# Power_Regulation.net
KiCad netlist of a schematic drawn in Altium Designer
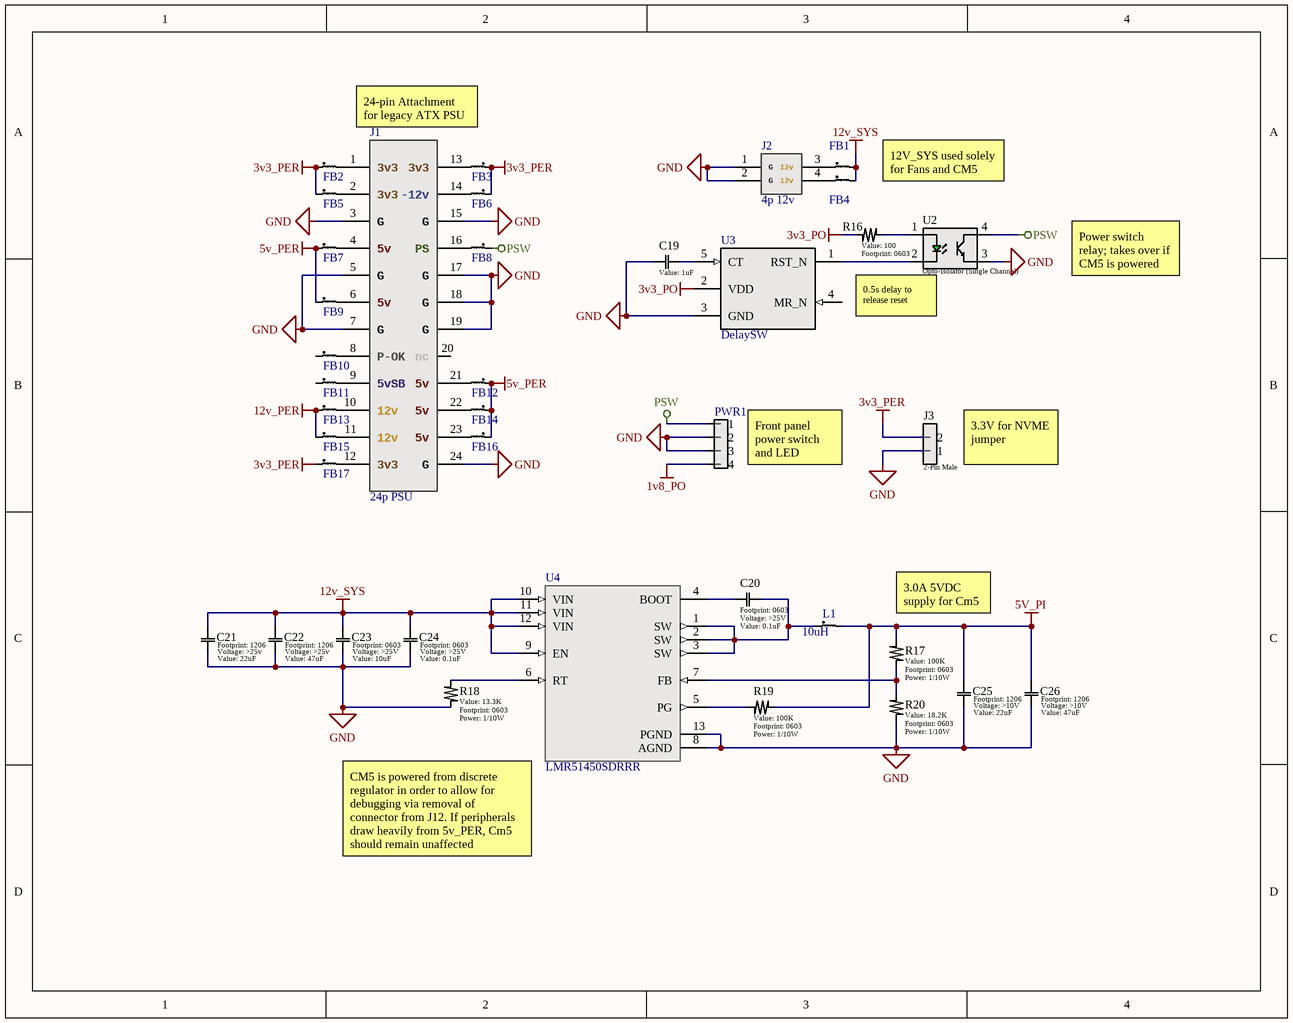
[diagram p0: Power_Regulation.SchDoc]

(export (version "E")
  (design (tool "Eeschema 10.0.6"))
  (components
    (comp (ref "C19")
      (value "1uF")
      (footprint "0603")
      (fields
        (field (name "VOLTAGE") "10V")
        (field (name "TOLERANCE") "10%")
        (field (name "Comment") "Generic Capacitor")
      )
      (libsource (lib "Capacitors") (part "Generic Capacitor"))
    )
    (comp (ref "C20")
      (value "0.1uF")
      (footprint "0603")
      (fields
        (field (name "VOLTAGE") ">25V")
        (field (name "TOLERANCE") "10%")
        (field (name "Comment") "Generic Capacitor")
      )
      (libsource (lib "Capacitors") (part "Generic Capacitor"))
    )
    (comp (ref "C21")
      (value "22uF")
      (footprint "1206")
      (fields
        (field (name "VOLTAGE") ">25v")
        (field (name "TOLERANCE") "20%")
        (field (name "Comment") "Generic Capacitor")
      )
      (libsource (lib "Capacitors") (part "Generic Capacitor"))
    )
    (comp (ref "C22")
      (value "47uF")
      (footprint "1206")
      (fields
        (field (name "VOLTAGE") ">25v")
        (field (name "TOLERANCE") "20%")
        (field (name "Comment") "Generic Capacitor")
      )
      (libsource (lib "Capacitors") (part "Generic Capacitor"))
    )
    (comp (ref "C23")
      (value "10uF")
      (footprint "0603")
      (fields
        (field (name "VOLTAGE") ">25V")
        (field (name "TOLERANCE") "10%")
        (field (name "Comment") "Generic Capacitor")
      )
      (libsource (lib "Capacitors") (part "Generic Capacitor"))
    )
    (comp (ref "C24")
      (value "0.1uF")
      (footprint "0603")
      (fields
        (field (name "VOLTAGE") ">25V")
        (field (name "TOLERANCE") "10%")
        (field (name "Comment") "Generic Capacitor")
      )
      (libsource (lib "Capacitors") (part "Generic Capacitor"))
    )
    (comp (ref "C25")
      (value "22uF")
      (footprint "1206")
      (fields
        (field (name "VOLTAGE") ">10V")
        (field (name "TOLERANCE") "20%")
        (field (name "Comment") "Generic Capacitor")
      )
      (libsource (lib "Capacitors") (part "Generic Capacitor"))
    )
    (comp (ref "C26")
      (value "47uF")
      (footprint "1206")
      (fields
        (field (name "VOLTAGE") ">10V")
        (field (name "TOLERANCE") "10%")
        (field (name "Comment") "Generic Capacitor")
      )
      (libsource (lib "Capacitors") (part "Generic Capacitor"))
    )
    (comp (ref "FB1")
      (value "1206 Ferrite")
      (footprint "1206")
      (description "160 Ohms @ 100MHz 1 Power, Signal Line Ferrite Bead 1206 (3216 Metric) 6A 18mOhm")
      (libsource (lib "Inductors") (part "HI1206T161R-10"))
    )
    (comp (ref "FB2")
      (value "1206 Ferrite")
      (footprint "1206")
      (description "160 Ohms @ 100MHz 1 Power, Signal Line Ferrite Bead 1206 (3216 Metric) 6A 18mOhm")
      (libsource (lib "Inductors") (part "HI1206T161R-10"))
    )
    (comp (ref "FB3")
      (value "1206 Ferrite")
      (footprint "1206")
      (description "160 Ohms @ 100MHz 1 Power, Signal Line Ferrite Bead 1206 (3216 Metric) 6A 18mOhm")
      (libsource (lib "") (part "HI1206T161R-10_1"))
    )
    (comp (ref "FB4")
      (value "1206 Ferrite")
      (footprint "1206")
      (description "160 Ohms @ 100MHz 1 Power, Signal Line Ferrite Bead 1206 (3216 Metric) 6A 18mOhm")
      (libsource (lib "Inductors") (part "HI1206T161R-10"))
    )
    (comp (ref "FB5")
      (value "1206 Ferrite")
      (footprint "1206")
      (description "160 Ohms @ 100MHz 1 Power, Signal Line Ferrite Bead 1206 (3216 Metric) 6A 18mOhm")
      (libsource (lib "Inductors") (part "HI1206T161R-10"))
    )
    (comp (ref "FB6")
      (value "1206 Ferrite")
      (footprint "1206")
      (description "160 Ohms @ 100MHz 1 Power, Signal Line Ferrite Bead 1206 (3216 Metric) 6A 18mOhm")
      (libsource (lib "") (part "HI1206T161R-10_1"))
    )
    (comp (ref "FB7")
      (value "1206 Ferrite")
      (footprint "1206")
      (description "160 Ohms @ 100MHz 1 Power, Signal Line Ferrite Bead 1206 (3216 Metric) 6A 18mOhm")
      (libsource (lib "Inductors") (part "HI1206T161R-10"))
    )
    (comp (ref "FB8")
      (value "1206 Ferrite")
      (footprint "1206")
      (description "160 Ohms @ 100MHz 1 Power, Signal Line Ferrite Bead 1206 (3216 Metric) 6A 18mOhm")
      (libsource (lib "") (part "HI1206T161R-10_1"))
    )
    (comp (ref "FB9")
      (value "1206 Ferrite")
      (footprint "1206")
      (description "160 Ohms @ 100MHz 1 Power, Signal Line Ferrite Bead 1206 (3216 Metric) 6A 18mOhm")
      (libsource (lib "Inductors") (part "HI1206T161R-10"))
    )
    (comp (ref "FB10")
      (value "1206 Ferrite")
      (footprint "1206")
      (description "160 Ohms @ 100MHz 1 Power, Signal Line Ferrite Bead 1206 (3216 Metric) 6A 18mOhm")
      (libsource (lib "Inductors") (part "HI1206T161R-10"))
    )
    (comp (ref "FB11")
      (value "1206 Ferrite")
      (footprint "1206")
      (description "160 Ohms @ 100MHz 1 Power, Signal Line Ferrite Bead 1206 (3216 Metric) 6A 18mOhm")
      (libsource (lib "Inductors") (part "HI1206T161R-10"))
    )
    (comp (ref "FB12")
      (value "1206 Ferrite")
      (footprint "1206")
      (description "160 Ohms @ 100MHz 1 Power, Signal Line Ferrite Bead 1206 (3216 Metric) 6A 18mOhm")
      (libsource (lib "") (part "HI1206T161R-10_1"))
    )
    (comp (ref "FB13")
      (value "1206 Ferrite")
      (footprint "1206")
      (description "160 Ohms @ 100MHz 1 Power, Signal Line Ferrite Bead 1206 (3216 Metric) 6A 18mOhm")
      (libsource (lib "Inductors") (part "HI1206T161R-10"))
    )
    (comp (ref "FB14")
      (value "1206 Ferrite")
      (footprint "1206")
      (description "160 Ohms @ 100MHz 1 Power, Signal Line Ferrite Bead 1206 (3216 Metric) 6A 18mOhm")
      (libsource (lib "") (part "HI1206T161R-10_1"))
    )
    (comp (ref "FB15")
      (value "1206 Ferrite")
      (footprint "1206")
      (description "160 Ohms @ 100MHz 1 Power, Signal Line Ferrite Bead 1206 (3216 Metric) 6A 18mOhm")
      (libsource (lib "Inductors") (part "HI1206T161R-10"))
    )
    (comp (ref "FB16")
      (value "1206 Ferrite")
      (footprint "1206")
      (description "160 Ohms @ 100MHz 1 Power, Signal Line Ferrite Bead 1206 (3216 Metric) 6A 18mOhm")
      (libsource (lib "") (part "HI1206T161R-10_1"))
    )
    (comp (ref "FB17")
      (value "1206 Ferrite")
      (footprint "1206")
      (description "160 Ohms @ 100MHz 1 Power, Signal Line Ferrite Bead 1206 (3216 Metric) 6A 18mOhm")
      (libsource (lib "Inductors") (part "HI1206T161R-10"))
    )
    (comp (ref "J1")
      (value "24p PSU")
      (footprint "CONN_442060007_MOL")
      (description "Connector Header Through Hole 24 position 0.165\" (4.20mm)")
      (libsource (lib "Connectors") (part "442060007"))
    )
    (comp (ref "J2")
      (value "4p 12v")
      (footprint "CON_39281043")
      (description "Connector Header Through Hole 4 position 0.165\" (4.20mm)")
      (libsource (lib "Connectors") (part "39281043"))
    )
    (comp (ref "J3")
      (value "2-Pin Male")
      (footprint "0022057025")
      (description "Conn Shrouded Header (4 Sides) HDR 2 POS 2.5mm Solder RA Thru-Hole SPOX™ Bag")
      (libsource (lib "Connectors") (part "0022057025"))
    )
    (comp (ref "L1")
      (value "10uH")
      (footprint "SMD 8.2x8.6mm")
      (description "5.1A 10uH ±20% 5.2A - Power Inductor")
      (fields
        (field (name "MANUFACTURER_PART_NUMBER") "IHLP3232DZER100M5A")
        (field (name "COPYRIGHT") "Copyright (C) 2023 Ultra Librarian. All rights reserved.")
      )
      (libsource (lib "Inductors") (part "IHLP3232DZER100M5A"))
    )
    (comp (ref "PWR1")
      (value "4-Pin Male Header (0.100\" Pitch)")
      (footprint "TSW-104-07-T-S")
      (description "Connector Header Through Hole 4 position 0.100\" (2.54mm)")
      (libsource (lib "Connectors") (part "TSW-104-07-T-S"))
    )
    (comp (ref "R16")
      (value "100")
      (footprint "0603")
      (fields
        (field (name "TOLERANCE") "1%")
        (field (name "POWER") "1/10W")
        (field (name "Comment") "Generic Resistor")
      )
      (libsource (lib "Resistors") (part "Generic Resistor"))
    )
    (comp (ref "R17")
      (value "100K")
      (footprint "0603")
      (fields
        (field (name "TOLERANCE") "1%")
        (field (name "POWER") "1/10W")
        (field (name "Comment") "Generic Resistor")
      )
      (libsource (lib "Resistors") (part "Generic Resistor"))
    )
    (comp (ref "R18")
      (value "13.3K")
      (footprint "0603")
      (fields
        (field (name "TOLERANCE") "1%")
        (field (name "POWER") "1/10W")
        (field (name "Comment") "Generic Resistor")
      )
      (libsource (lib "Resistors") (part "Generic Resistor"))
    )
    (comp (ref "R19")
      (value "100K")
      (footprint "0603")
      (fields
        (field (name "TOLERANCE") "1%")
        (field (name "POWER") "1/10W")
        (field (name "Comment") "Generic Resistor")
      )
      (libsource (lib "Resistors") (part "Generic Resistor"))
    )
    (comp (ref "R20")
      (value "18.2K")
      (footprint "0603")
      (fields
        (field (name "TOLERANCE") "1%")
        (field (name "POWER") "1/10W")
        (field (name "Comment") "Generic Resistor")
      )
      (libsource (lib "Resistors") (part "Generic Resistor"))
    )
    (comp (ref "U2")
      (value "Opto-Isolator (Single Channel)")
      (footprint "4-SMD (7.62mm Gull-Wing) Opto-Transistor")
      (description "LTV Series Single Channel 80 V 5000 Vrms Transistor Output Optocoupler SMT-DIP-4")
      (fields
        (field (name "MANUFACTURER") "Vishay Lite-On")
        (field (name "MANUFACTURER PART NUMBER") "LTV-816S-TA1")
      )
      (libsource (lib "Switches") (part "LTV-816S"))
    )
    (comp (ref "U3")
      (value "DelaySW")
      (footprint "TSOT-23-5")
      (description "Supervisor Open Drain or Open Collector 1 Channel SOT-23-5\r\n2.2V Threshold")
      (libsource (lib "Switches") (part "TPS3840DL22DBVR"))
    )
    (comp (ref "U4")
      (value "LMR51450SDRRR")
      (footprint "WSON-12")
      (description "36-V, 5-A synchronous buck converter")
      (fields (field (name "MF") "Texas Instruments"))
      (libsource (lib "Regulators") (part "LMR51450SDRRR"))
    )
  )
  (nets
    (net (code "1") (name "1v8_PO") (class "Default")
      (node (ref "PWR1") (pin "4") (pinfunction "4_4") (pintype "passive"))
    )
    (net (code "2") (name "3v3_PER") (class "Default")
      (node (ref "FB17") (pin "1") (pinfunction "1_1") (pintype "passive"))
      (node (ref "FB2") (pin "1") (pinfunction "1_1") (pintype "passive"))
      (node (ref "FB3") (pin "1") (pinfunction "1_1") (pintype "passive"))
      (node (ref "FB5") (pin "1") (pinfunction "1_1") (pintype "passive"))
      (node (ref "FB6") (pin "1") (pinfunction "1_1") (pintype "passive"))
      (node (ref "J3") (pin "2") (pinfunction "2_2") (pintype "passive"))
    )
    (net (code "3") (name "3v3_PO") (class "Default")
      (node (ref "R16") (pin "1") (pinfunction "1_1") (pintype "passive"))
      (node (ref "U3") (pin "2") (pinfunction "VDD_2") (pintype "power_in"))
    )
    (net (code "4") (name "5V_PI") (class "Default")
      (node (ref "C25") (pin "1") (pinfunction "1_1") (pintype "passive"))
      (node (ref "C26") (pin "1") (pinfunction "1_1") (pintype "passive"))
      (node (ref "L1") (pin "2") (pinfunction "2_2") (pintype "passive"))
      (node (ref "R17") (pin "2") (pinfunction "2_2") (pintype "passive"))
      (node (ref "R19") (pin "1") (pinfunction "1_1") (pintype "passive"))
    )
    (net (code "5") (name "5v_PER") (class "Default")
      (node (ref "FB12") (pin "1") (pinfunction "1_1") (pintype "passive"))
      (node (ref "FB14") (pin "1") (pinfunction "1_1") (pintype "passive"))
      (node (ref "FB16") (pin "1") (pinfunction "1_1") (pintype "passive"))
      (node (ref "FB7") (pin "1") (pinfunction "1_1") (pintype "passive"))
      (node (ref "FB9") (pin "1") (pinfunction "1_1") (pintype "passive"))
    )
    (net (code "6") (name "12v_PER") (class "Default")
      (node (ref "FB13") (pin "1") (pinfunction "1_1") (pintype "passive"))
      (node (ref "FB15") (pin "1") (pinfunction "1_1") (pintype "passive"))
    )
    (net (code "7") (name "12v_SYS") (class "Default")
      (node (ref "C21") (pin "1") (pinfunction "1_1") (pintype "passive"))
      (node (ref "C22") (pin "1") (pinfunction "1_1") (pintype "passive"))
      (node (ref "C23") (pin "1") (pinfunction "1_1") (pintype "passive"))
      (node (ref "C24") (pin "1") (pinfunction "1_1") (pintype "passive"))
      (node (ref "FB1") (pin "2") (pinfunction "2_2") (pintype "passive"))
      (node (ref "FB4") (pin "2") (pinfunction "2_2") (pintype "passive"))
      (node (ref "U4") (pin "10") (pinfunction "VIN_10") (pintype "input"))
      (node (ref "U4") (pin "11") (pinfunction "VIN_11") (pintype "input"))
      (node (ref "U4") (pin "12") (pinfunction "VIN_12") (pintype "input"))
      (node (ref "U4") (pin "9") (pinfunction "EN_9") (pintype "input"))
    )
    (net (code "8") (name "GND") (class "Default")
      (node (ref "C19") (pin "2") (pinfunction "2_2") (pintype "passive"))
      (node (ref "C21") (pin "2") (pinfunction "2_2") (pintype "passive"))
      (node (ref "C22") (pin "2") (pinfunction "2_2") (pintype "passive"))
      (node (ref "C23") (pin "2") (pinfunction "2_2") (pintype "passive"))
      (node (ref "C24") (pin "2") (pinfunction "2_2") (pintype "passive"))
      (node (ref "C25") (pin "2") (pinfunction "2_2") (pintype "passive"))
      (node (ref "C26") (pin "2") (pinfunction "2_2") (pintype "passive"))
      (node (ref "J1") (pin "15") (pinfunction "G_15") (pintype "passive"))
      (node (ref "J1") (pin "17") (pinfunction "G_17") (pintype "passive"))
      (node (ref "J1") (pin "18") (pinfunction "G_18") (pintype "passive"))
      (node (ref "J1") (pin "19") (pinfunction "G_19") (pintype "passive"))
      (node (ref "J1") (pin "24") (pinfunction "G_24") (pintype "passive"))
      (node (ref "J1") (pin "3") (pinfunction "G_3") (pintype "passive"))
      (node (ref "J1") (pin "5") (pinfunction "G_5") (pintype "passive"))
      (node (ref "J1") (pin "7") (pinfunction "G_7") (pintype "passive"))
      (node (ref "J2") (pin "1") (pinfunction "G_1") (pintype "passive"))
      (node (ref "J2") (pin "2") (pinfunction "G_2") (pintype "passive"))
      (node (ref "J3") (pin "1") (pinfunction "1_1") (pintype "passive"))
      (node (ref "PWR1") (pin "2") (pinfunction "2_2") (pintype "passive"))
      (node (ref "PWR1") (pin "3") (pinfunction "3_3") (pintype "passive"))
      (node (ref "R18") (pin "1") (pinfunction "1_1") (pintype "passive"))
      (node (ref "R20") (pin "1") (pinfunction "1_1") (pintype "passive"))
      (node (ref "U2") (pin "3") (pinfunction "3_3") (pintype "passive"))
      (node (ref "U3") (pin "3") (pinfunction "GND_3") (pintype "power_in"))
      (node (ref "U4") (pin "13") (pinfunction "PGND_13") (pintype "power_in"))
      (node (ref "U4") (pin "8") (pinfunction "AGND_8") (pintype "power_in"))
    )
    (net (code "9") (name "Net-(C20-Pad2)") (class "Default")
      (node (ref "C20") (pin "2") (pinfunction "2_2") (pintype "passive"))
      (node (ref "L1") (pin "1") (pinfunction "1_1") (pintype "passive"))
      (node (ref "U4") (pin "1") (pinfunction "SW_1") (pintype "output"))
      (node (ref "U4") (pin "2") (pinfunction "SW_2") (pintype "output"))
      (node (ref "U4") (pin "3") (pinfunction "SW_3") (pintype "output"))
    )
    (net (code "10") (name "Net-(FB1-Pad1)") (class "Default")
      (node (ref "FB1") (pin "1") (pinfunction "1_1") (pintype "passive"))
      (node (ref "J2") (pin "3") (pinfunction "12v_3") (pintype "passive"))
    )
    (net (code "11") (name "Net-(FB2-Pad2)") (class "Default")
      (node (ref "FB2") (pin "2") (pinfunction "2_2") (pintype "passive"))
      (node (ref "J1") (pin "1") (pinfunction "3v3_1") (pintype "passive"))
    )
    (net (code "12") (name "Net-(FB3-Pad2)") (class "Default")
      (node (ref "FB3") (pin "2") (pinfunction "2_2") (pintype "passive"))
      (node (ref "J1") (pin "13") (pinfunction "3v3_13") (pintype "passive"))
    )
    (net (code "13") (name "Net-(FB4-Pad1)") (class "Default")
      (node (ref "FB4") (pin "1") (pinfunction "1_1") (pintype "passive"))
      (node (ref "J2") (pin "4") (pinfunction "12v_4") (pintype "passive"))
    )
    (net (code "14") (name "Net-(FB5-Pad2)") (class "Default")
      (node (ref "FB5") (pin "2") (pinfunction "2_2") (pintype "passive"))
      (node (ref "J1") (pin "2") (pinfunction "3v3_2") (pintype "passive"))
    )
    (net (code "15") (name "Net-(FB7-Pad2)") (class "Default")
      (node (ref "FB7") (pin "2") (pinfunction "2_2") (pintype "passive"))
      (node (ref "J1") (pin "4") (pinfunction "5v_4") (pintype "passive"))
    )
    (net (code "16") (name "Net-(FB9-Pad2)") (class "Default")
      (node (ref "FB9") (pin "2") (pinfunction "2_2") (pintype "passive"))
      (node (ref "J1") (pin "6") (pinfunction "5v_6") (pintype "passive"))
    )
    (net (code "17") (name "Net-(FB12-Pad2)") (class "Default")
      (node (ref "FB12") (pin "2") (pinfunction "2_2") (pintype "passive"))
      (node (ref "J1") (pin "21") (pinfunction "5v_21") (pintype "passive"))
    )
    (net (code "18") (name "Net-(FB13-Pad2)") (class "Default")
      (node (ref "FB13") (pin "2") (pinfunction "2_2") (pintype "passive"))
      (node (ref "J1") (pin "10") (pinfunction "12v_10") (pintype "passive"))
    )
    (net (code "19") (name "Net-(FB14-Pad2)") (class "Default")
      (node (ref "FB14") (pin "2") (pinfunction "2_2") (pintype "passive"))
      (node (ref "J1") (pin "22") (pinfunction "5v_22") (pintype "passive"))
    )
    (net (code "20") (name "Net-(FB15-Pad2)") (class "Default")
      (node (ref "FB15") (pin "2") (pinfunction "2_2") (pintype "passive"))
      (node (ref "J1") (pin "11") (pinfunction "12v_11") (pintype "passive"))
    )
    (net (code "21") (name "Net-(FB16-Pad2)") (class "Default")
      (node (ref "FB16") (pin "2") (pinfunction "2_2") (pintype "passive"))
      (node (ref "J1") (pin "23") (pinfunction "5v_23") (pintype "passive"))
    )
    (net (code "22") (name "Net-(FB17-Pad2)") (class "Default")
      (node (ref "FB17") (pin "2") (pinfunction "2_2") (pintype "passive"))
      (node (ref "J1") (pin "12") (pinfunction "3v3_12") (pintype "passive"))
    )
    (net (code "23") (name "Net-(J1--12v)") (class "Default")
      (node (ref "FB6") (pin "2") (pinfunction "2_2") (pintype "passive"))
      (node (ref "J1") (pin "14") (pinfunction "-12v_14") (pintype "passive"))
    )
    (net (code "24") (name "Net-(J1-5vSB)") (class "Default")
      (node (ref "FB11") (pin "2") (pinfunction "2_2") (pintype "passive"))
      (node (ref "J1") (pin "9") (pinfunction "5vSB_9") (pintype "passive"))
    )
    (net (code "25") (name "Net-(J1-P-OK)") (class "Default")
      (node (ref "FB10") (pin "2") (pinfunction "2_2") (pintype "passive"))
      (node (ref "J1") (pin "8") (pinfunction "P-OK_8") (pintype "passive"))
    )
    (net (code "26") (name "Net-(J1-PS)") (class "Default")
      (node (ref "FB8") (pin "2") (pinfunction "2_2") (pintype "passive"))
      (node (ref "J1") (pin "16") (pinfunction "PS_16") (pintype "passive"))
    )
    (net (code "27") (name "Net-(R16-Pad2)") (class "Default")
      (node (ref "R16") (pin "2") (pinfunction "2_2") (pintype "passive"))
      (node (ref "U2") (pin "1") (pinfunction "1_1") (pintype "passive"))
    )
    (net (code "28") (name "Net-(U3-CT)") (class "Default")
      (node (ref "C19") (pin "1") (pinfunction "1_1") (pintype "passive"))
      (node (ref "U3") (pin "5") (pinfunction "CT_5") (pintype "input"))
    )
    (net (code "29") (name "Net-(U3-RST_N)") (class "Default")
      (node (ref "U2") (pin "2") (pinfunction "2_2") (pintype "passive"))
      (node (ref "U3") (pin "1") (pinfunction "RST_N_1") (pintype "open_collector"))
    )
    (net (code "30") (name "Net-(U4-BOOT)") (class "Default")
      (node (ref "C20") (pin "1") (pinfunction "1_1") (pintype "passive"))
      (node (ref "U4") (pin "4") (pinfunction "BOOT_4") (pintype "passive"))
    )
    (net (code "31") (name "Net-(U4-FB)") (class "Default")
      (node (ref "R17") (pin "1") (pinfunction "1_1") (pintype "passive"))
      (node (ref "R20") (pin "2") (pinfunction "2_2") (pintype "passive"))
      (node (ref "U4") (pin "7") (pinfunction "FB_7") (pintype "input"))
    )
    (net (code "32") (name "Net-(U4-PG)") (class "Default")
      (node (ref "R19") (pin "2") (pinfunction "2_2") (pintype "passive"))
      (node (ref "U4") (pin "5") (pinfunction "PG_5") (pintype "output"))
    )
    (net (code "33") (name "Net-(U4-RT)") (class "Default")
      (node (ref "R18") (pin "2") (pinfunction "2_2") (pintype "passive"))
      (node (ref "U4") (pin "6") (pinfunction "RT_6") (pintype "input"))
    )
    (net (code "34") (name "PSW") (class "Default")
      (node (ref "FB8") (pin "1") (pinfunction "1_1") (pintype "passive"))
      (node (ref "PWR1") (pin "1") (pinfunction "1_1") (pintype "passive"))
      (node (ref "U2") (pin "4") (pinfunction "4_4") (pintype "passive"))
    )
    (net (code "35") (name "unconnected-(FB10-Pad1)") (class "Default")
      (node (ref "FB10") (pin "1") (pinfunction "1_1") (pintype "passive"))
    )
    (net (code "36") (name "unconnected-(FB11-Pad1)") (class "Default")
      (node (ref "FB11") (pin "1") (pinfunction "1_1") (pintype "passive"))
    )
    (net (code "37") (name "unconnected-(J1-nc-Pad20)") (class "Default")
      (node (ref "J1") (pin "20") (pinfunction "nc_20") (pintype "passive"))
    )
    (net (code "38") (name "unconnected-(U3-MR_N-Pad4)") (class "Default")
      (node (ref "U3") (pin "4") (pinfunction "MR_N_4") (pintype "input"))
    )
  )
)
